# power.net
KiCad netlist of a schematic drawn in Altium Designer
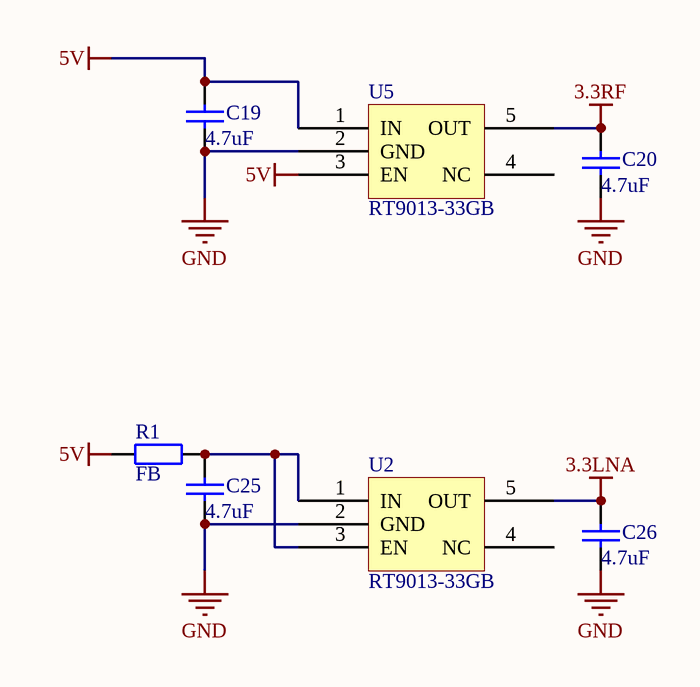
[diagram p0: power.SchDoc]

(export (version "E")
  (design (tool "Eeschema 10.0.6"))
  (components
    (comp (ref "C19")
      (value "4.7uF")
      (footprint "0603")
      (description "Capacitor")
      (fields (field (name "PUBLISHER") "Altium Limited"))
      (libsource (lib "RTC6705") (part "Cap"))
    )
    (comp (ref "C20")
      (value "4.7uF")
      (footprint "0603")
      (description "Capacitor")
      (fields (field (name "PUBLISHER") "Altium Limited"))
      (libsource (lib "RTC6705") (part "Cap"))
    )
    (comp (ref "C25")
      (value "4.7uF")
      (footprint "0603")
      (description "Capacitor")
      (fields (field (name "PUBLISHER") "Altium Limited"))
      (libsource (lib "RTC6705") (part "Cap"))
    )
    (comp (ref "C26")
      (value "4.7uF")
      (footprint "0603")
      (description "Capacitor")
      (fields (field (name "PUBLISHER") "Altium Limited"))
      (libsource (lib "RTC6705") (part "Cap"))
    )
    (comp (ref "R1")
      (value "FB")
      (footprint "0402")
      (description "Resistor")
      (fields (field (name "PUBLISHER") "Altium Limited"))
      (libsource (lib "Miscellaneous Devices") (part "Res2"))
    )
    (comp (ref "U2") (value "RT9013-33GB") (footprint "SOT23-5") (libsource (lib "RTC6705") (part "LP5907")))
    (comp (ref "U5") (value "RT9013-33GB") (footprint "SOT23-5") (libsource (lib "RTC6705") (part "LP5907")))
  )
  (nets
    (net (code "1") (name "3.3LNA") (class "Default")
      (node (ref "C26") (pin "2") (pinfunction "2_2") (pintype "passive"))
      (node (ref "U2") (pin "5") (pinfunction "OUT_5") (pintype "passive"))
    )
    (net (code "2") (name "3.3RF") (class "Default")
      (node (ref "C20") (pin "2") (pinfunction "2_2") (pintype "passive"))
      (node (ref "U5") (pin "5") (pinfunction "OUT_5") (pintype "passive"))
    )
    (net (code "3") (name "5V") (class "Default")
      (node (ref "C19") (pin "2") (pinfunction "2_2") (pintype "passive"))
      (node (ref "R1") (pin "2") (pinfunction "2_2") (pintype "passive"))
      (node (ref "U5") (pin "1") (pinfunction "IN_1") (pintype "passive"))
      (node (ref "U5") (pin "3") (pinfunction "EN_3") (pintype "passive"))
    )
    (net (code "4") (name "GND") (class "Default")
      (node (ref "C19") (pin "1") (pinfunction "1_1") (pintype "passive"))
      (node (ref "C20") (pin "1") (pinfunction "1_1") (pintype "passive"))
      (node (ref "C25") (pin "1") (pinfunction "1_1") (pintype "passive"))
      (node (ref "C26") (pin "1") (pinfunction "1_1") (pintype "passive"))
      (node (ref "U2") (pin "2") (pinfunction "GND_2") (pintype "passive"))
      (node (ref "U5") (pin "2") (pinfunction "GND_2") (pintype "passive"))
    )
    (net (code "5") (name "Net-(U2-EN)") (class "Default")
      (node (ref "C25") (pin "2") (pinfunction "2_2") (pintype "passive"))
      (node (ref "R1") (pin "1") (pinfunction "1_1") (pintype "passive"))
      (node (ref "U2") (pin "1") (pinfunction "IN_1") (pintype "passive"))
      (node (ref "U2") (pin "3") (pinfunction "EN_3") (pintype "passive"))
    )
    (net (code "6") (name "unconnected-(U2-NC-Pad4)") (class "Default")
      (node (ref "U2") (pin "4") (pinfunction "NC_4") (pintype "passive"))
    )
    (net (code "7") (name "unconnected-(U5-NC-Pad4)") (class "Default")
      (node (ref "U5") (pin "4") (pinfunction "NC_4") (pintype "passive"))
    )
  )
)
